# HarpTransistors_3v.net
KiCad netlist of a schematic drawn in EAGLE
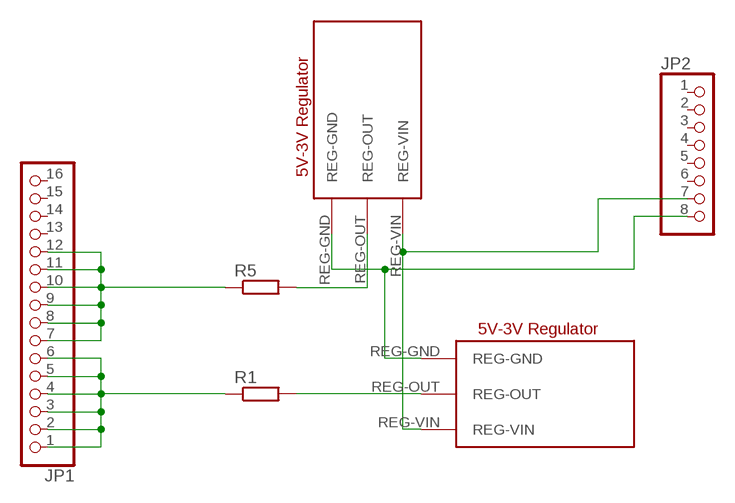
[diagram p0: schematic, sheet 1]

(export (version "E")
  (design (tool "Eeschema 10.0.6"))
  (components
    (comp (ref "JP1")
      (value "PINHD-1X16")
      (footprint "eagle-import:1X16")
      (libsource (lib "eagle-import") (part "PINHD-1X16"))
    )
    (comp (ref "JP2")
      (value "PINHD-1X8")
      (footprint "eagle-import:1X08")
      (libsource (lib "eagle-import") (part "PINHD-1X8"))
    )
    (comp (ref "R1")
      (value "R-EU_0204/5")
      (footprint "eagle-import:0204_5")
      (libsource (lib "eagle-import") (part "R-EU_0204/5"))
    )
    (comp (ref "R5")
      (value "R-EU_0204/5")
      (footprint "eagle-import:0204_5")
      (libsource (lib "eagle-import") (part "R-EU_0204/5"))
    )
    (comp (ref "U$1")
      (value "5V-TO-3V-REG-DEV")
      (footprint "eagle-import:5V-TO-3V-REG-PAC")
      (libsource (lib "eagle-import") (part "5V-TO-3V-REG-DEV"))
    )
    (comp (ref "U$2")
      (value "5V-TO-3V-REG-DEV")
      (footprint "eagle-import:5V-TO-3V-REG-PAC")
      (libsource (lib "eagle-import") (part "5V-TO-3V-REG-DEV"))
    )
  )
  (nets
    (net (code "1") (name "Net-(JP1-Pad1)") (class "Default")
      (node (ref "JP1") (pin "1") (pinfunction "1_1") (pintype "passive"))
      (node (ref "JP1") (pin "2") (pinfunction "2_2") (pintype "passive"))
      (node (ref "JP1") (pin "3") (pinfunction "3_3") (pintype "passive"))
      (node (ref "JP1") (pin "4") (pinfunction "4_4") (pintype "passive"))
      (node (ref "JP1") (pin "5") (pinfunction "5_5") (pintype "passive"))
      (node (ref "JP1") (pin "6") (pinfunction "6_6") (pintype "passive"))
      (node (ref "R1") (pin "1") (pinfunction "1_1") (pintype "passive"))
    )
    (net (code "2") (name "Net-(JP1-Pad10)") (class "Default")
      (node (ref "JP1") (pin "10") (pinfunction "10_10") (pintype "passive"))
      (node (ref "JP1") (pin "11") (pinfunction "11_11") (pintype "passive"))
      (node (ref "JP1") (pin "12") (pinfunction "12_12") (pintype "passive"))
      (node (ref "JP1") (pin "7") (pinfunction "7_7") (pintype "passive"))
      (node (ref "JP1") (pin "8") (pinfunction "8_8") (pintype "passive"))
      (node (ref "JP1") (pin "9") (pinfunction "9_9") (pintype "passive"))
      (node (ref "R5") (pin "1") (pinfunction "1_1") (pintype "passive"))
    )
    (net (code "3") (name "Net-(JP2-Pad7)") (class "Default")
      (node (ref "JP2") (pin "7") (pinfunction "7_7") (pintype "passive"))
      (node (ref "U$1") (pin "REG-VIN") (pinfunction "REG-VIN_REG-VIN") (pintype "power_in"))
      (node (ref "U$2") (pin "REG-VIN") (pinfunction "REG-VIN_REG-VIN") (pintype "power_in"))
    )
    (net (code "4") (name "Net-(JP2-Pad8)") (class "Default")
      (node (ref "JP2") (pin "8") (pinfunction "8_8") (pintype "passive"))
      (node (ref "U$1") (pin "REG-GND") (pinfunction "REG-GND_REG-GND") (pintype "bidirectional"))
      (node (ref "U$2") (pin "REG-GND") (pinfunction "REG-GND_REG-GND") (pintype "bidirectional"))
    )
    (net (code "5") (name "Net-(R1-Pad2)") (class "Default")
      (node (ref "R1") (pin "2") (pinfunction "2_2") (pintype "passive"))
      (node (ref "U$2") (pin "REG-OUT") (pinfunction "REG-OUT_REG-OUT") (pintype "power_in"))
    )
    (net (code "6") (name "Net-(R5-Pad2)") (class "Default")
      (node (ref "R5") (pin "2") (pinfunction "2_2") (pintype "passive"))
      (node (ref "U$1") (pin "REG-OUT") (pinfunction "REG-OUT_REG-OUT") (pintype "power_in"))
    )
    (net (code "7") (name "unconnected-(JP1-Pad13)") (class "Default")
      (node (ref "JP1") (pin "13") (pinfunction "13_13") (pintype "passive"))
    )
    (net (code "8") (name "unconnected-(JP1-Pad14)") (class "Default")
      (node (ref "JP1") (pin "14") (pinfunction "14_14") (pintype "passive"))
    )
    (net (code "9") (name "unconnected-(JP1-Pad15)") (class "Default")
      (node (ref "JP1") (pin "15") (pinfunction "15_15") (pintype "passive"))
    )
    (net (code "10") (name "unconnected-(JP1-Pad16)") (class "Default")
      (node (ref "JP1") (pin "16") (pinfunction "16_16") (pintype "passive"))
    )
    (net (code "11") (name "unconnected-(JP2-Pad1)") (class "Default")
      (node (ref "JP2") (pin "1") (pinfunction "1_1") (pintype "passive"))
    )
    (net (code "12") (name "unconnected-(JP2-Pad2)") (class "Default")
      (node (ref "JP2") (pin "2") (pinfunction "2_2") (pintype "passive"))
    )
    (net (code "13") (name "unconnected-(JP2-Pad3)") (class "Default")
      (node (ref "JP2") (pin "3") (pinfunction "3_3") (pintype "passive"))
    )
    (net (code "14") (name "unconnected-(JP2-Pad4)") (class "Default")
      (node (ref "JP2") (pin "4") (pinfunction "4_4") (pintype "passive"))
    )
    (net (code "15") (name "unconnected-(JP2-Pad5)") (class "Default")
      (node (ref "JP2") (pin "5") (pinfunction "5_5") (pintype "passive"))
    )
    (net (code "16") (name "unconnected-(JP2-Pad6)") (class "Default")
      (node (ref "JP2") (pin "6") (pinfunction "6_6") (pintype "passive"))
    )
  )
)
